# VIBRO.net
KiCad netlist of a schematic drawn in Altium Designer
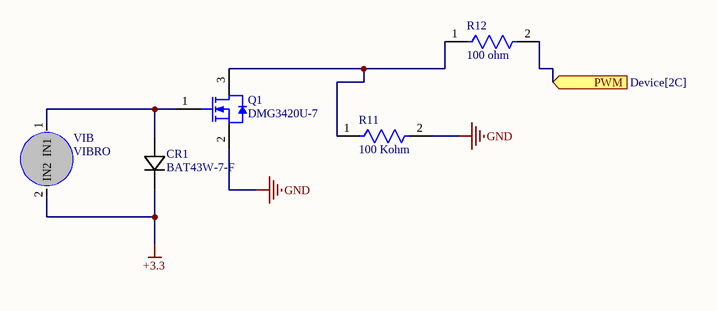
[diagram p0: VIBRO.SchDoc]

(export (version "E")
  (design (tool "Eeschema 10.0.6"))
  (components
    (comp (ref "CR1")
      (value "BAT43W-7-F")
      (footprint "SOD123_DIO")
      (fields (field (name "COPYRIGHT") "Copyright (C) 2023 Ultra Librarian. All rights reserved."))
      (libsource (lib "ANT") (part "BAT43W-7-F"))
    )
    (comp (ref "Q1")
      (value "DMG3420U-7")
      (footprint "DIOD-SOT23-3_B_V")
      (description "N-Channel Enhancement Mode MOSFET, 20 V, -55 to 150 degC, 3-Pin SOT23, RoHS, Tape and Reel")
      (fields (field (name "MANUFACTURER") "Diodes Inc"))
      (libsource (lib "Altium Content Vault") (part "NEMOS-GSD-3"))
    )
    (comp (ref "R11")
      (value "100 Kohm")
      (footprint "FP-RC1005-IPC_C")
      (description "Res Thick Film 0402 1.87kΩ 1% 0.063W ±100ppm/°C Molded SMD T/R")
      (fields (field (name "TOLERANCE") "1%"))
      (libsource (lib "Altium Content Vault") (part "1029c3af85768c4190bb7ad29bc67b5"))
    )
    (comp (ref "R12")
      (value "100 ohm")
      (footprint "FP-RC1005-IPC_C")
      (description "Res Thick Film 0402 1.87kΩ 1% 0.063W ±100ppm/°C Molded SMD T/R")
      (fields (field (name "TOLERANCE") "1%"))
      (libsource (lib "Altium Content Vault") (part "1029c3af85768c4190bb7ad29bc67b5"))
    )
    (comp (ref "VIB") (value "VIBRO") (footprint "VIBRO") (libsource (lib "ANT") (part "VIBRO")))
  )
  (nets
    (net (code "1") (name "+3.3") (class "Default")
      (node (ref "CR1") (pin "1") (pinfunction "1_1") (pintype "passive"))
      (node (ref "VIB") (pin "2") (pinfunction "IN2_2") (pintype "passive"))
    )
    (net (code "2") (name "/PWM") (class "Default")
      (node (ref "R12") (pin "2") (pinfunction "2_2") (pintype "passive"))
    )
    (net (code "3") (name "GND") (class "Default")
      (node (ref "Q1") (pin "2") (pinfunction "S_2") (pintype "passive"))
      (node (ref "R11") (pin "2") (pinfunction "2_2") (pintype "passive"))
    )
    (net (code "4") (name "Net-(Q1-D)") (class "Default")
      (node (ref "Q1") (pin "3") (pinfunction "D_3") (pintype "passive"))
      (node (ref "R11") (pin "1") (pinfunction "1_1") (pintype "passive"))
      (node (ref "R12") (pin "1") (pinfunction "1_1") (pintype "passive"))
    )
    (net (code "5") (name "Net-(Q1-G)") (class "Default")
      (node (ref "CR1") (pin "2") (pinfunction "2_2") (pintype "passive"))
      (node (ref "Q1") (pin "1") (pinfunction "G_1") (pintype "passive"))
      (node (ref "VIB") (pin "1") (pinfunction "IN1_1") (pintype "passive"))
    )
  )
)
